# sch_Power.net
KiCad netlist of a schematic drawn in Altium Designer
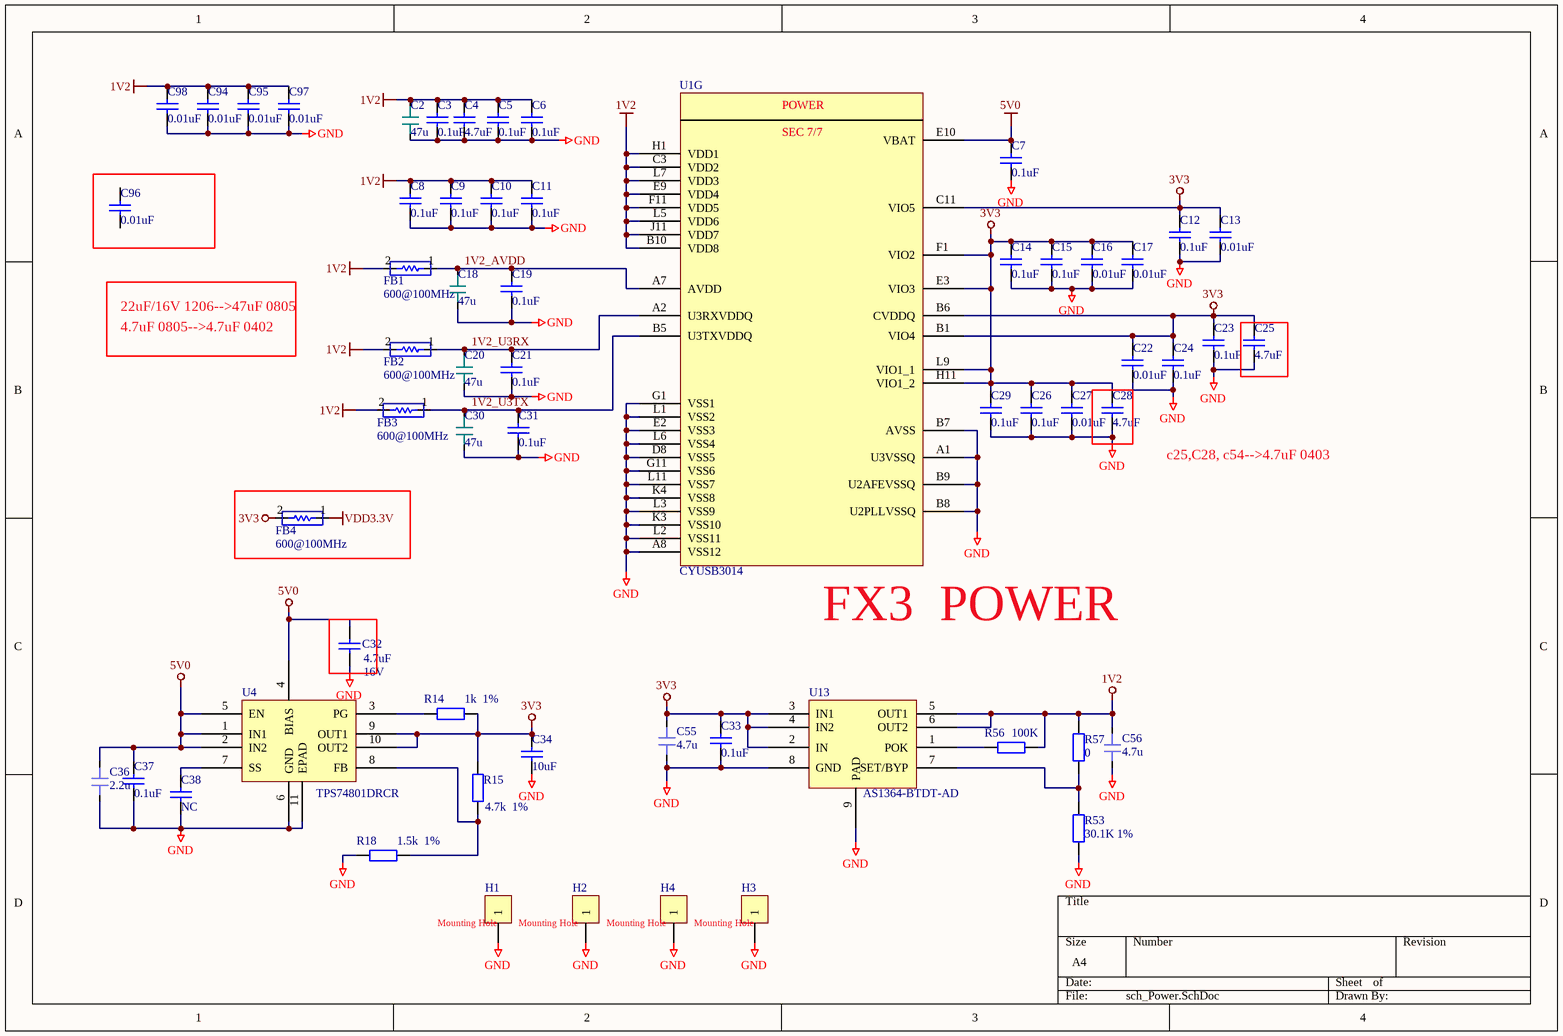
[diagram p0: sch_Power.SchDoc]

(export (version "E")
  (design (tool "Eeschema 10.0.6"))
  (components
    (comp (ref "C2")
      (value "47u")
      (footprint "0805C")
      (description "CC08052B476M5B20D")
      (libsource (lib "V0P1") (part "cap0805"))
    )
    (comp (ref "C3")
      (value "0.1uF")
      (footprint "0402C")
      (description "Capacitor")
      (fields (field (name "PUBLISHER") "Altium Limited"))
      (libsource (lib "Miscellaneous Devices") (part "Cap"))
    )
    (comp (ref "C4")
      (value "4.7uF")
      (footprint "0402C")
      (description "Capacitor")
      (fields (field (name "Comment") "0.1uF") (field (name "PUBLISHER") "Altium Limited"))
      (libsource (lib "Miscellaneous Devices") (part "Cap"))
    )
    (comp (ref "C5")
      (value "0.1uF")
      (footprint "0402C")
      (description "Capacitor")
      (fields (field (name "PUBLISHER") "Altium Limited"))
      (libsource (lib "Miscellaneous Devices") (part "Cap"))
    )
    (comp (ref "C6")
      (value "0.1uF")
      (footprint "0402C")
      (description "Capacitor")
      (fields (field (name "PUBLISHER") "Altium Limited"))
      (libsource (lib "Miscellaneous Devices") (part "Cap"))
    )
    (comp (ref "C7")
      (value "0.1uF")
      (footprint "0402C")
      (description "Capacitor")
      (fields (field (name "PUBLISHER") "Altium Limited"))
      (libsource (lib "Miscellaneous Devices") (part "Cap"))
    )
    (comp (ref "C8")
      (value "0.1uF")
      (footprint "0402C")
      (description "Capacitor")
      (fields (field (name "PUBLISHER") "Altium Limited"))
      (libsource (lib "Miscellaneous Devices") (part "Cap"))
    )
    (comp (ref "C9")
      (value "0.1uF")
      (footprint "0402C")
      (description "Capacitor")
      (fields (field (name "PUBLISHER") "Altium Limited"))
      (libsource (lib "Miscellaneous Devices") (part "Cap"))
    )
    (comp (ref "C10")
      (value "0.1uF")
      (footprint "0402C")
      (description "Capacitor")
      (fields (field (name "PUBLISHER") "Altium Limited"))
      (libsource (lib "Miscellaneous Devices") (part "Cap"))
    )
    (comp (ref "C11")
      (value "0.1uF")
      (footprint "0402C")
      (description "Capacitor")
      (fields (field (name "PUBLISHER") "Altium Limited"))
      (libsource (lib "Miscellaneous Devices") (part "Cap"))
    )
    (comp (ref "C12")
      (value "0.1uF")
      (footprint "0402C")
      (description "Capacitor")
      (fields (field (name "PUBLISHER") "Altium Limited"))
      (libsource (lib "Miscellaneous Devices") (part "Cap"))
    )
    (comp (ref "C13")
      (value "0.01uF")
      (footprint "0402C")
      (description "Capacitor")
      (fields (field (name "PUBLISHER") "Altium Limited"))
      (libsource (lib "Miscellaneous Devices") (part "Cap"))
    )
    (comp (ref "C14")
      (value "0.1uF")
      (footprint "0402C")
      (description "Capacitor")
      (fields (field (name "PUBLISHER") "Altium Limited"))
      (libsource (lib "Miscellaneous Devices") (part "Cap"))
    )
    (comp (ref "C15")
      (value "0.1uF")
      (footprint "0402C")
      (description "Capacitor")
      (fields (field (name "PUBLISHER") "Altium Limited"))
      (libsource (lib "Miscellaneous Devices") (part "Cap"))
    )
    (comp (ref "C16")
      (value "0.01uF")
      (footprint "0402C")
      (description "Capacitor")
      (fields (field (name "PUBLISHER") "Altium Limited"))
      (libsource (lib "Miscellaneous Devices") (part "Cap"))
    )
    (comp (ref "C17")
      (value "0.01uF")
      (footprint "0402C")
      (description "Capacitor")
      (fields (field (name "PUBLISHER") "Altium Limited"))
      (libsource (lib "Miscellaneous Devices") (part "Cap"))
    )
    (comp (ref "C18")
      (value "47u")
      (footprint "0805C")
      (description "CC08052B476M5B20D")
      (libsource (lib "V0P1") (part "cap0805"))
    )
    (comp (ref "C19")
      (value "0.1uF")
      (footprint "0402C")
      (description "Capacitor")
      (fields (field (name "PUBLISHER") "Altium Limited"))
      (libsource (lib "Miscellaneous Devices") (part "Cap"))
    )
    (comp (ref "C20")
      (value "47u")
      (footprint "0805C")
      (description "CC08052B476M5B20D")
      (libsource (lib "V0P1") (part "cap0805"))
    )
    (comp (ref "C21")
      (value "0.1uF")
      (footprint "0402C")
      (description "Capacitor")
      (fields (field (name "PUBLISHER") "Altium Limited"))
      (libsource (lib "Miscellaneous Devices") (part "Cap"))
    )
    (comp (ref "C22")
      (value "0.01uF")
      (footprint "0402C")
      (description "Capacitor")
      (fields (field (name "PUBLISHER") "Altium Limited"))
      (libsource (lib "Miscellaneous Devices") (part "Cap"))
    )
    (comp (ref "C23")
      (value "0.1uF")
      (footprint "0402C")
      (description "Capacitor")
      (fields (field (name "PUBLISHER") "Altium Limited"))
      (libsource (lib "Miscellaneous Devices") (part "Cap"))
    )
    (comp (ref "C24")
      (value "0.1uF")
      (footprint "0402C")
      (description "Capacitor")
      (fields (field (name "PUBLISHER") "Altium Limited"))
      (libsource (lib "Miscellaneous Devices") (part "Cap"))
    )
    (comp (ref "C25")
      (value "4.7uF")
      (footprint "0402C")
      (description "Capacitor")
      (fields (field (name "PUBLISHER") "Altium Limited"))
      (libsource (lib "Miscellaneous Devices") (part "Cap"))
    )
    (comp (ref "C26")
      (value "0.1uF")
      (footprint "0402C")
      (description "Capacitor")
      (fields (field (name "PUBLISHER") "Altium Limited"))
      (libsource (lib "Miscellaneous Devices") (part "Cap"))
    )
    (comp (ref "C27")
      (value "0.01uF")
      (footprint "0402C")
      (description "Capacitor")
      (fields (field (name "PUBLISHER") "Altium Limited"))
      (libsource (lib "Miscellaneous Devices") (part "Cap"))
    )
    (comp (ref "C28")
      (value "4.7uF")
      (footprint "0402C")
      (description "Capacitor")
      (fields (field (name "PUBLISHER") "Altium Limited"))
      (libsource (lib "Miscellaneous Devices") (part "Cap"))
    )
    (comp (ref "C29")
      (value "0.1uF")
      (footprint "0402C")
      (description "Capacitor")
      (fields (field (name "PUBLISHER") "Altium Limited"))
      (libsource (lib "Miscellaneous Devices") (part "Cap"))
    )
    (comp (ref "C30")
      (value "47u")
      (footprint "0805C")
      (description "CC08052B476M5B20D")
      (libsource (lib "V0P1") (part "cap0805"))
    )
    (comp (ref "C31")
      (value "0.1uF")
      (footprint "0402C")
      (description "Capacitor")
      (fields (field (name "PUBLISHER") "Altium Limited"))
      (libsource (lib "Miscellaneous Devices") (part "Cap"))
    )
    (comp (ref "C32")
      (value "4.7uF")
      (footprint "0402C")
      (description "Capacitor")
      (fields (field (name "ALTIUM_VALUE") "16V") (field (name "PUBLISHER") "Altium Limited"))
      (libsource (lib "Miscellaneous Devices") (part "Cap"))
    )
    (comp (ref "C33")
      (value "0.1uF")
      (footprint "0402C")
      (description "Capacitor")
      (fields (field (name "PUBLISHER") "Altium Limited"))
      (libsource (lib "Miscellaneous Devices") (part "Cap"))
    )
    (comp (ref "C34")
      (value "10uF")
      (footprint "0805C")
      (description "Capacitor")
      (fields (field (name "PUBLISHER") "Altium Limited"))
      (libsource (lib "Miscellaneous Devices") (part "Cap"))
    )
    (comp (ref "C36")
      (value "2.2u")
      (footprint "0402C")
      (description "CC0402MRX5R5BB475")
      (libsource (lib "V0P1") (part "cap0402"))
    )
    (comp (ref "C37")
      (value "0.1uF")
      (footprint "0402C")
      (description "Capacitor")
      (fields (field (name "PUBLISHER") "Altium Limited"))
      (libsource (lib "Miscellaneous Devices") (part "Cap"))
    )
    (comp (ref "C38")
      (value "NC")
      (footprint "0402C")
      (description "Capacitor")
      (fields (field (name "PUBLISHER") "Altium Limited"))
      (libsource (lib "Miscellaneous Devices") (part "Cap"))
    )
    (comp (ref "C55")
      (value "4.7u")
      (footprint "0402C")
      (description "CC0402MRX5R5BB475")
      (libsource (lib "V0P1") (part "cap0402"))
    )
    (comp (ref "C56")
      (value "4.7u")
      (footprint "0402C")
      (description "CC0402MRX5R5BB475")
      (libsource (lib "V0P1") (part "cap0402"))
    )
    (comp (ref "C94")
      (value "0.01uF")
      (footprint "0402C")
      (description "Capacitor")
      (fields (field (name "PUBLISHER") "Altium Limited"))
      (libsource (lib "Miscellaneous Devices") (part "Cap"))
    )
    (comp (ref "C95")
      (value "0.01uF")
      (footprint "0402C")
      (description "Capacitor")
      (fields (field (name "PUBLISHER") "Altium Limited"))
      (libsource (lib "Miscellaneous Devices") (part "Cap"))
    )
    (comp (ref "C96")
      (value "0.01uF")
      (footprint "0402C")
      (description "Capacitor")
      (fields (field (name "PUBLISHER") "Altium Limited"))
      (libsource (lib "Miscellaneous Devices") (part "Cap"))
    )
    (comp (ref "C97")
      (value "0.01uF")
      (footprint "0402C")
      (description "Capacitor")
      (fields (field (name "PUBLISHER") "Altium Limited"))
      (libsource (lib "Miscellaneous Devices") (part "Cap"))
    )
    (comp (ref "C98")
      (value "0.01uF")
      (footprint "0402C")
      (description "Capacitor")
      (fields (field (name "PUBLISHER") "Altium Limited"))
      (libsource (lib "Miscellaneous Devices") (part "Cap"))
    )
    (comp (ref "FB1") (value "600@100MHz") (footprint "0603R") (libsource (lib "TXW") (part "600@100MHz")))
    (comp (ref "FB2") (value "600@100MHz") (footprint "0603R") (libsource (lib "TXW") (part "600@100MHz")))
    (comp (ref "FB3") (value "600@100MHz") (footprint "0603R") (libsource (lib "TXW") (part "600@100MHz")))
    (comp (ref "FB4") (value "600@100MHz") (footprint "0603R") (libsource (lib "TXW") (part "600@100MHz")))
    (comp (ref "H1")
      (value "CON1")
      (footprint "PAD_M3_D350_450")
      (description "Connector")
      (libsource (lib "SuperSchLib") (part "CON1"))
    )
    (comp (ref "H2")
      (value "CON1")
      (footprint "PAD_M3_D350_450")
      (description "Connector")
      (libsource (lib "SuperSchLib") (part "CON1"))
    )
    (comp (ref "H3")
      (value "CON1")
      (footprint "PAD_M3_D350_450")
      (description "Connector")
      (libsource (lib "SuperSchLib") (part "CON1"))
    )
    (comp (ref "H4")
      (value "CON1")
      (footprint "PAD_M3_D350_450")
      (description "Connector")
      (libsource (lib "SuperSchLib") (part "CON1"))
    )
    (comp (ref "R14")
      (value "1k  1%")
      (footprint "0402R")
      (description "Resistor")
      (fields (field (name "Comment") "1K") (field (name "PUBLISHER") "Altium Limited"))
      (libsource (lib "SZG") (part "Resistor"))
    )
    (comp (ref "R15")
      (value "4.7k  1%")
      (footprint "0402R")
      (description "Resistor")
      (fields (field (name "Comment") "4.7K") (field (name "PUBLISHER") "Altium Limited"))
      (libsource (lib "") (part "Resistor_1"))
    )
    (comp (ref "R18")
      (value "1.5k  1%")
      (footprint "0402R")
      (description "Resistor")
      (fields (field (name "Comment") "1.5K") (field (name "PUBLISHER") "Altium Limited"))
      (libsource (lib "SZG") (part "Resistor"))
    )
    (comp (ref "R53")
      (value "30.1K 1%")
      (footprint "0402R")
      (description "Resistor")
      (fields (field (name "Comment") "30.1K") (field (name "PUBLISHER") "Altium Limited"))
      (libsource (lib "") (part "Resistor_1"))
    )
    (comp (ref "R56")
      (value "100K")
      (footprint "0402R")
      (description "Resistor")
      (fields (field (name "PUBLISHER") "Altium Limited"))
      (libsource (lib "SZG") (part "Resistor"))
    )
    (comp (ref "R57")
      (value "0")
      (footprint "0402R")
      (description "Resistor")
      (fields (field (name "Comment") "0R") (field (name "PUBLISHER") "Altium Limited"))
      (libsource (lib "") (part "Resistor_1"))
    )
    (comp (ref "U1")
      (value "CYUSB3014")
      (footprint "FBGA121_P80L100W100H11")
      (libsource (lib "TXW") (part "CYUSB3014"))
    )
    (comp (ref "U4")
      (value "TPS74801DRCR")
      (footprint "SON10_P50L32W32H10_DRC")
      (libsource (lib "TXW") (part "TPS74801DRCR"))
    )
    (comp (ref "U13")
      (value "AS1364-BTDT-AD")
      (footprint "TDFN8_P65L30W30H08")
      (libsource (lib "TXW") (part "AS1364-BTDT-AD"))
    )
  )
  (nets
    (net (code "1") (name "/1V2_AVDD") (class "Default")
      (node (ref "C18") (pin "1") (pinfunction "1_1") (pintype "passive"))
      (node (ref "C19") (pin "2") (pinfunction "2_2") (pintype "passive"))
      (node (ref "FB1") (pin "1") (pinfunction "1_1") (pintype "passive"))
      (node (ref "U1") (pin "A7") (pinfunction "AVDD_A7") (pintype "passive"))
    )
    (net (code "2") (name "/1V2_U3RX") (class "Default")
      (node (ref "C20") (pin "1") (pinfunction "1_1") (pintype "passive"))
      (node (ref "C21") (pin "2") (pinfunction "2_2") (pintype "passive"))
      (node (ref "FB2") (pin "1") (pinfunction "1_1") (pintype "passive"))
      (node (ref "U1") (pin "A2") (pinfunction "U3RXVDDQ_A2") (pintype "passive"))
    )
    (net (code "3") (name "/1V2_U3TX") (class "Default")
      (node (ref "C30") (pin "1") (pinfunction "1_1") (pintype "passive"))
      (node (ref "C31") (pin "2") (pinfunction "2_2") (pintype "passive"))
      (node (ref "FB3") (pin "1") (pinfunction "1_1") (pintype "passive"))
      (node (ref "U1") (pin "B5") (pinfunction "U3TXVDDQ_B5") (pintype "passive"))
    )
    (net (code "4") (name "1V2") (class "Default")
      (node (ref "C10") (pin "2") (pinfunction "2_2") (pintype "passive"))
      (node (ref "C11") (pin "2") (pinfunction "2_2") (pintype "passive"))
      (node (ref "C2") (pin "1") (pinfunction "1_1") (pintype "passive"))
      (node (ref "C3") (pin "2") (pinfunction "2_2") (pintype "passive"))
      (node (ref "C4") (pin "2") (pinfunction "2_2") (pintype "passive"))
      (node (ref "C5") (pin "2") (pinfunction "2_2") (pintype "passive"))
      (node (ref "C56") (pin "1") (pinfunction "1_1") (pintype "passive"))
      (node (ref "C6") (pin "2") (pinfunction "2_2") (pintype "passive"))
      (node (ref "C8") (pin "2") (pinfunction "2_2") (pintype "passive"))
      (node (ref "C9") (pin "2") (pinfunction "2_2") (pintype "passive"))
      (node (ref "C94") (pin "2") (pinfunction "2_2") (pintype "passive"))
      (node (ref "C95") (pin "2") (pinfunction "2_2") (pintype "passive"))
      (node (ref "C97") (pin "2") (pinfunction "2_2") (pintype "passive"))
      (node (ref "C98") (pin "2") (pinfunction "2_2") (pintype "passive"))
      (node (ref "FB1") (pin "2") (pinfunction "2_2") (pintype "passive"))
      (node (ref "FB2") (pin "2") (pinfunction "2_2") (pintype "passive"))
      (node (ref "FB3") (pin "2") (pinfunction "2_2") (pintype "passive"))
      (node (ref "R56") (pin "1") (pinfunction "1_1") (pintype "passive"))
      (node (ref "R57") (pin "1") (pinfunction "1_1") (pintype "passive"))
      (node (ref "U1") (pin "B10") (pinfunction "VDD8_B10") (pintype "passive"))
      (node (ref "U1") (pin "C3") (pinfunction "VDD2_C3") (pintype "passive"))
      (node (ref "U1") (pin "E9") (pinfunction "VDD4_E9") (pintype "passive"))
      (node (ref "U1") (pin "F11") (pinfunction "VDD5_F11") (pintype "passive"))
      (node (ref "U1") (pin "H1") (pinfunction "VDD1_H1") (pintype "passive"))
      (node (ref "U1") (pin "J11") (pinfunction "VDD7_J11") (pintype "passive"))
      (node (ref "U1") (pin "L5") (pinfunction "VDD6_L5") (pintype "passive"))
      (node (ref "U1") (pin "L7") (pinfunction "VDD3_L7") (pintype "passive"))
      (node (ref "U13") (pin "5") (pinfunction "OUT1_5") (pintype "passive"))
      (node (ref "U13") (pin "6") (pinfunction "OUT2_6") (pintype "passive"))
    )
    (net (code "5") (name "3V3") (class "Default")
      (node (ref "C12") (pin "2") (pinfunction "2_2") (pintype "passive"))
      (node (ref "C13") (pin "2") (pinfunction "2_2") (pintype "passive"))
      (node (ref "C14") (pin "2") (pinfunction "2_2") (pintype "passive"))
      (node (ref "C15") (pin "2") (pinfunction "2_2") (pintype "passive"))
      (node (ref "C16") (pin "2") (pinfunction "2_2") (pintype "passive"))
      (node (ref "C17") (pin "2") (pinfunction "2_2") (pintype "passive"))
      (node (ref "C22") (pin "2") (pinfunction "2_2") (pintype "passive"))
      (node (ref "C23") (pin "2") (pinfunction "2_2") (pintype "passive"))
      (node (ref "C24") (pin "2") (pinfunction "2_2") (pintype "passive"))
      (node (ref "C25") (pin "2") (pinfunction "2_2") (pintype "passive"))
      (node (ref "C26") (pin "2") (pinfunction "2_2") (pintype "passive"))
      (node (ref "C27") (pin "2") (pinfunction "2_2") (pintype "passive"))
      (node (ref "C28") (pin "2") (pinfunction "2_2") (pintype "passive"))
      (node (ref "C29") (pin "2") (pinfunction "2_2") (pintype "passive"))
      (node (ref "C33") (pin "2") (pinfunction "2_2") (pintype "passive"))
      (node (ref "C34") (pin "2") (pinfunction "2_2") (pintype "passive"))
      (node (ref "C55") (pin "1") (pinfunction "1_1") (pintype "passive"))
      (node (ref "FB4") (pin "2") (pinfunction "2_2") (pintype "passive"))
      (node (ref "R14") (pin "1") (pinfunction "1_1") (pintype "passive"))
      (node (ref "R15") (pin "1") (pinfunction "1_1") (pintype "passive"))
      (node (ref "U1") (pin "B1") (pinfunction "VIO4_B1") (pintype "passive"))
      (node (ref "U1") (pin "B6") (pinfunction "CVDDQ_B6") (pintype "passive"))
      (node (ref "U1") (pin "C11") (pinfunction "VIO5_C11") (pintype "power_in"))
      (node (ref "U1") (pin "E3") (pinfunction "VIO3_E3") (pintype "passive"))
      (node (ref "U1") (pin "F1") (pinfunction "VIO2_F1") (pintype "passive"))
      (node (ref "U1") (pin "H11") (pinfunction "VIO1_2_H11") (pintype "passive"))
      (node (ref "U1") (pin "L9") (pinfunction "VIO1_1_L9") (pintype "passive"))
      (node (ref "U13") (pin "2") (pinfunction "IN_2") (pintype "passive"))
      (node (ref "U13") (pin "3") (pinfunction "IN1_3") (pintype "passive"))
      (node (ref "U13") (pin "4") (pinfunction "IN2_4") (pintype "passive"))
      (node (ref "U4") (pin "10") (pinfunction "OUT2_10") (pintype "passive"))
      (node (ref "U4") (pin "9") (pinfunction "OUT1_9") (pintype "passive"))
    )
    (net (code "6") (name "5V0") (class "Default")
      (node (ref "C32") (pin "1") (pinfunction "1_1") (pintype "passive"))
      (node (ref "C36") (pin "1") (pinfunction "1_1") (pintype "passive"))
      (node (ref "C37") (pin "2") (pinfunction "2_2") (pintype "passive"))
      (node (ref "C7") (pin "2") (pinfunction "2_2") (pintype "passive"))
      (node (ref "U1") (pin "E10") (pinfunction "VBAT_E10") (pintype "passive"))
      (node (ref "U4") (pin "1") (pinfunction "IN1_1") (pintype "passive"))
      (node (ref "U4") (pin "2") (pinfunction "IN2_2") (pintype "passive"))
      (node (ref "U4") (pin "4") (pinfunction "BIAS_4") (pintype "passive"))
      (node (ref "U4") (pin "5") (pinfunction "EN_5") (pintype "passive"))
    )
    (net (code "7") (name "GND") (class "Default")
      (node (ref "C10") (pin "1") (pinfunction "1_1") (pintype "passive"))
      (node (ref "C11") (pin "1") (pinfunction "1_1") (pintype "passive"))
      (node (ref "C12") (pin "1") (pinfunction "1_1") (pintype "passive"))
      (node (ref "C13") (pin "1") (pinfunction "1_1") (pintype "passive"))
      (node (ref "C14") (pin "1") (pinfunction "1_1") (pintype "passive"))
      (node (ref "C15") (pin "1") (pinfunction "1_1") (pintype "passive"))
      (node (ref "C16") (pin "1") (pinfunction "1_1") (pintype "passive"))
      (node (ref "C17") (pin "1") (pinfunction "1_1") (pintype "passive"))
      (node (ref "C18") (pin "2") (pinfunction "2_2") (pintype "passive"))
      (node (ref "C19") (pin "1") (pinfunction "1_1") (pintype "passive"))
      (node (ref "C2") (pin "2") (pinfunction "2_2") (pintype "passive"))
      (node (ref "C20") (pin "2") (pinfunction "2_2") (pintype "passive"))
      (node (ref "C21") (pin "1") (pinfunction "1_1") (pintype "passive"))
      (node (ref "C22") (pin "1") (pinfunction "1_1") (pintype "passive"))
      (node (ref "C23") (pin "1") (pinfunction "1_1") (pintype "passive"))
      (node (ref "C24") (pin "1") (pinfunction "1_1") (pintype "passive"))
      (node (ref "C25") (pin "1") (pinfunction "1_1") (pintype "passive"))
      (node (ref "C26") (pin "1") (pinfunction "1_1") (pintype "passive"))
      (node (ref "C27") (pin "1") (pinfunction "1_1") (pintype "passive"))
      (node (ref "C28") (pin "1") (pinfunction "1_1") (pintype "passive"))
      (node (ref "C29") (pin "1") (pinfunction "1_1") (pintype "passive"))
      (node (ref "C3") (pin "1") (pinfunction "1_1") (pintype "passive"))
      (node (ref "C30") (pin "2") (pinfunction "2_2") (pintype "passive"))
      (node (ref "C31") (pin "1") (pinfunction "1_1") (pintype "passive"))
      (node (ref "C32") (pin "2") (pinfunction "2_2") (pintype "passive"))
      (node (ref "C33") (pin "1") (pinfunction "1_1") (pintype "passive"))
      (node (ref "C34") (pin "1") (pinfunction "1_1") (pintype "passive"))
      (node (ref "C36") (pin "2") (pinfunction "2_2") (pintype "passive"))
      (node (ref "C37") (pin "1") (pinfunction "1_1") (pintype "passive"))
      (node (ref "C38") (pin "1") (pinfunction "1_1") (pintype "passive"))
      (node (ref "C4") (pin "1") (pinfunction "1_1") (pintype "passive"))
      (node (ref "C5") (pin "1") (pinfunction "1_1") (pintype "passive"))
      (node (ref "C55") (pin "2") (pinfunction "2_2") (pintype "passive"))
      (node (ref "C56") (pin "2") (pinfunction "2_2") (pintype "passive"))
      (node (ref "C6") (pin "1") (pinfunction "1_1") (pintype "passive"))
      (node (ref "C7") (pin "1") (pinfunction "1_1") (pintype "passive"))
      (node (ref "C8") (pin "1") (pinfunction "1_1") (pintype "passive"))
      (node (ref "C9") (pin "1") (pinfunction "1_1") (pintype "passive"))
      (node (ref "C94") (pin "1") (pinfunction "1_1") (pintype "passive"))
      (node (ref "C95") (pin "1") (pinfunction "1_1") (pintype "passive"))
      (node (ref "C97") (pin "1") (pinfunction "1_1") (pintype "passive"))
      (node (ref "C98") (pin "1") (pinfunction "1_1") (pintype "passive"))
      (node (ref "H1") (pin "1") (pinfunction "1_1") (pintype "passive"))
      (node (ref "H2") (pin "1") (pinfunction "1_1") (pintype "passive"))
      (node (ref "H3") (pin "1") (pinfunction "1_1") (pintype "passive"))
      (node (ref "H4") (pin "1") (pinfunction "1_1") (pintype "passive"))
      (node (ref "R18") (pin "2") (pinfunction "2_2") (pintype "passive"))
      (node (ref "R53") (pin "2") (pinfunction "2_2") (pintype "passive"))
      (node (ref "U1") (pin "A1") (pinfunction "U3VSSQ_A1") (pintype "passive"))
      (node (ref "U1") (pin "A8") (pinfunction "VSS12_A8") (pintype "passive"))
      (node (ref "U1") (pin "B7") (pinfunction "AVSS_B7") (pintype "passive"))
      (node (ref "U1") (pin "B8") (pinfunction "U2PLLVSSQ_B8") (pintype "passive"))
      (node (ref "U1") (pin "B9") (pinfunction "U2AFEVSSQ_B9") (pintype "passive"))
      (node (ref "U1") (pin "D8") (pinfunction "VSS5_D8") (pintype "passive"))
      (node (ref "U1") (pin "E2") (pinfunction "VSS3_E2") (pintype "passive"))
      (node (ref "U1") (pin "G1") (pinfunction "VSS1_G1") (pintype "passive"))
      (node (ref "U1") (pin "G11") (pinfunction "VSS6_G11") (pintype "passive"))
      (node (ref "U1") (pin "K3") (pinfunction "VSS10_K3") (pintype "passive"))
      (node (ref "U1") (pin "K4") (pinfunction "VSS8_K4") (pintype "passive"))
      (node (ref "U1") (pin "L1") (pinfunction "VSS2_L1") (pintype "passive"))
      (node (ref "U1") (pin "L11") (pinfunction "VSS7_L11") (pintype "passive"))
      (node (ref "U1") (pin "L2") (pinfunction "VSS11_L2") (pintype "passive"))
      (node (ref "U1") (pin "L3") (pinfunction "VSS9_L3") (pintype "passive"))
      (node (ref "U1") (pin "L6") (pinfunction "VSS4_L6") (pintype "passive"))
      (node (ref "U13") (pin "8") (pinfunction "GND_8") (pintype "passive"))
      (node (ref "U13") (pin "9") (pinfunction "PAD_9") (pintype "passive"))
      (node (ref "U4") (pin "11") (pinfunction "EPAD_11") (pintype "passive"))
      (node (ref "U4") (pin "6") (pinfunction "GND_6") (pintype "passive"))
    )
    (net (code "8") (name "Net-(U4-FB)") (class "Default")
      (node (ref "R15") (pin "2") (pinfunction "2_2") (pintype "passive"))
      (node (ref "R18") (pin "1") (pinfunction "1_1") (pintype "passive"))
      (node (ref "U4") (pin "8") (pinfunction "FB_8") (pintype "passive"))
    )
    (net (code "9") (name "Net-(U4-PG)") (class "Default")
      (node (ref "R14") (pin "2") (pinfunction "2_2") (pintype "passive"))
      (node (ref "U4") (pin "3") (pinfunction "PG_3") (pintype "passive"))
    )
    (net (code "10") (name "Net-(U4-SS)") (class "Default")
      (node (ref "C38") (pin "2") (pinfunction "2_2") (pintype "passive"))
      (node (ref "U4") (pin "7") (pinfunction "SS_7") (pintype "passive"))
    )
    (net (code "11") (name "Net-(U13-POK)") (class "Default")
      (node (ref "R56") (pin "2") (pinfunction "2_2") (pintype "passive"))
      (node (ref "U13") (pin "1") (pinfunction "POK_1") (pintype "passive"))
    )
    (net (code "12") (name "Net-(U13-SET{slash}BYP)") (class "Default")
      (node (ref "R53") (pin "1") (pinfunction "1_1") (pintype "passive"))
      (node (ref "R57") (pin "2") (pinfunction "2_2") (pintype "passive"))
      (node (ref "U13") (pin "7") (pinfunction "SET/BYP_7") (pintype "passive"))
    )
    (net (code "13") (name "VDD3.3V") (class "Default")
      (node (ref "FB4") (pin "1") (pinfunction "1_1") (pintype "passive"))
    )
    (net (code "14") (name "unconnected-(C96-Pad1)") (class "Default")
      (node (ref "C96") (pin "1") (pinfunction "1_1") (pintype "passive"))
    )
    (net (code "15") (name "unconnected-(C96-Pad2)") (class "Default")
      (node (ref "C96") (pin "2") (pinfunction "2_2") (pintype "passive"))
    )
  )
)
